# 6x5keyboard.net
KiCad netlist of a schematic drawn in EAGLE
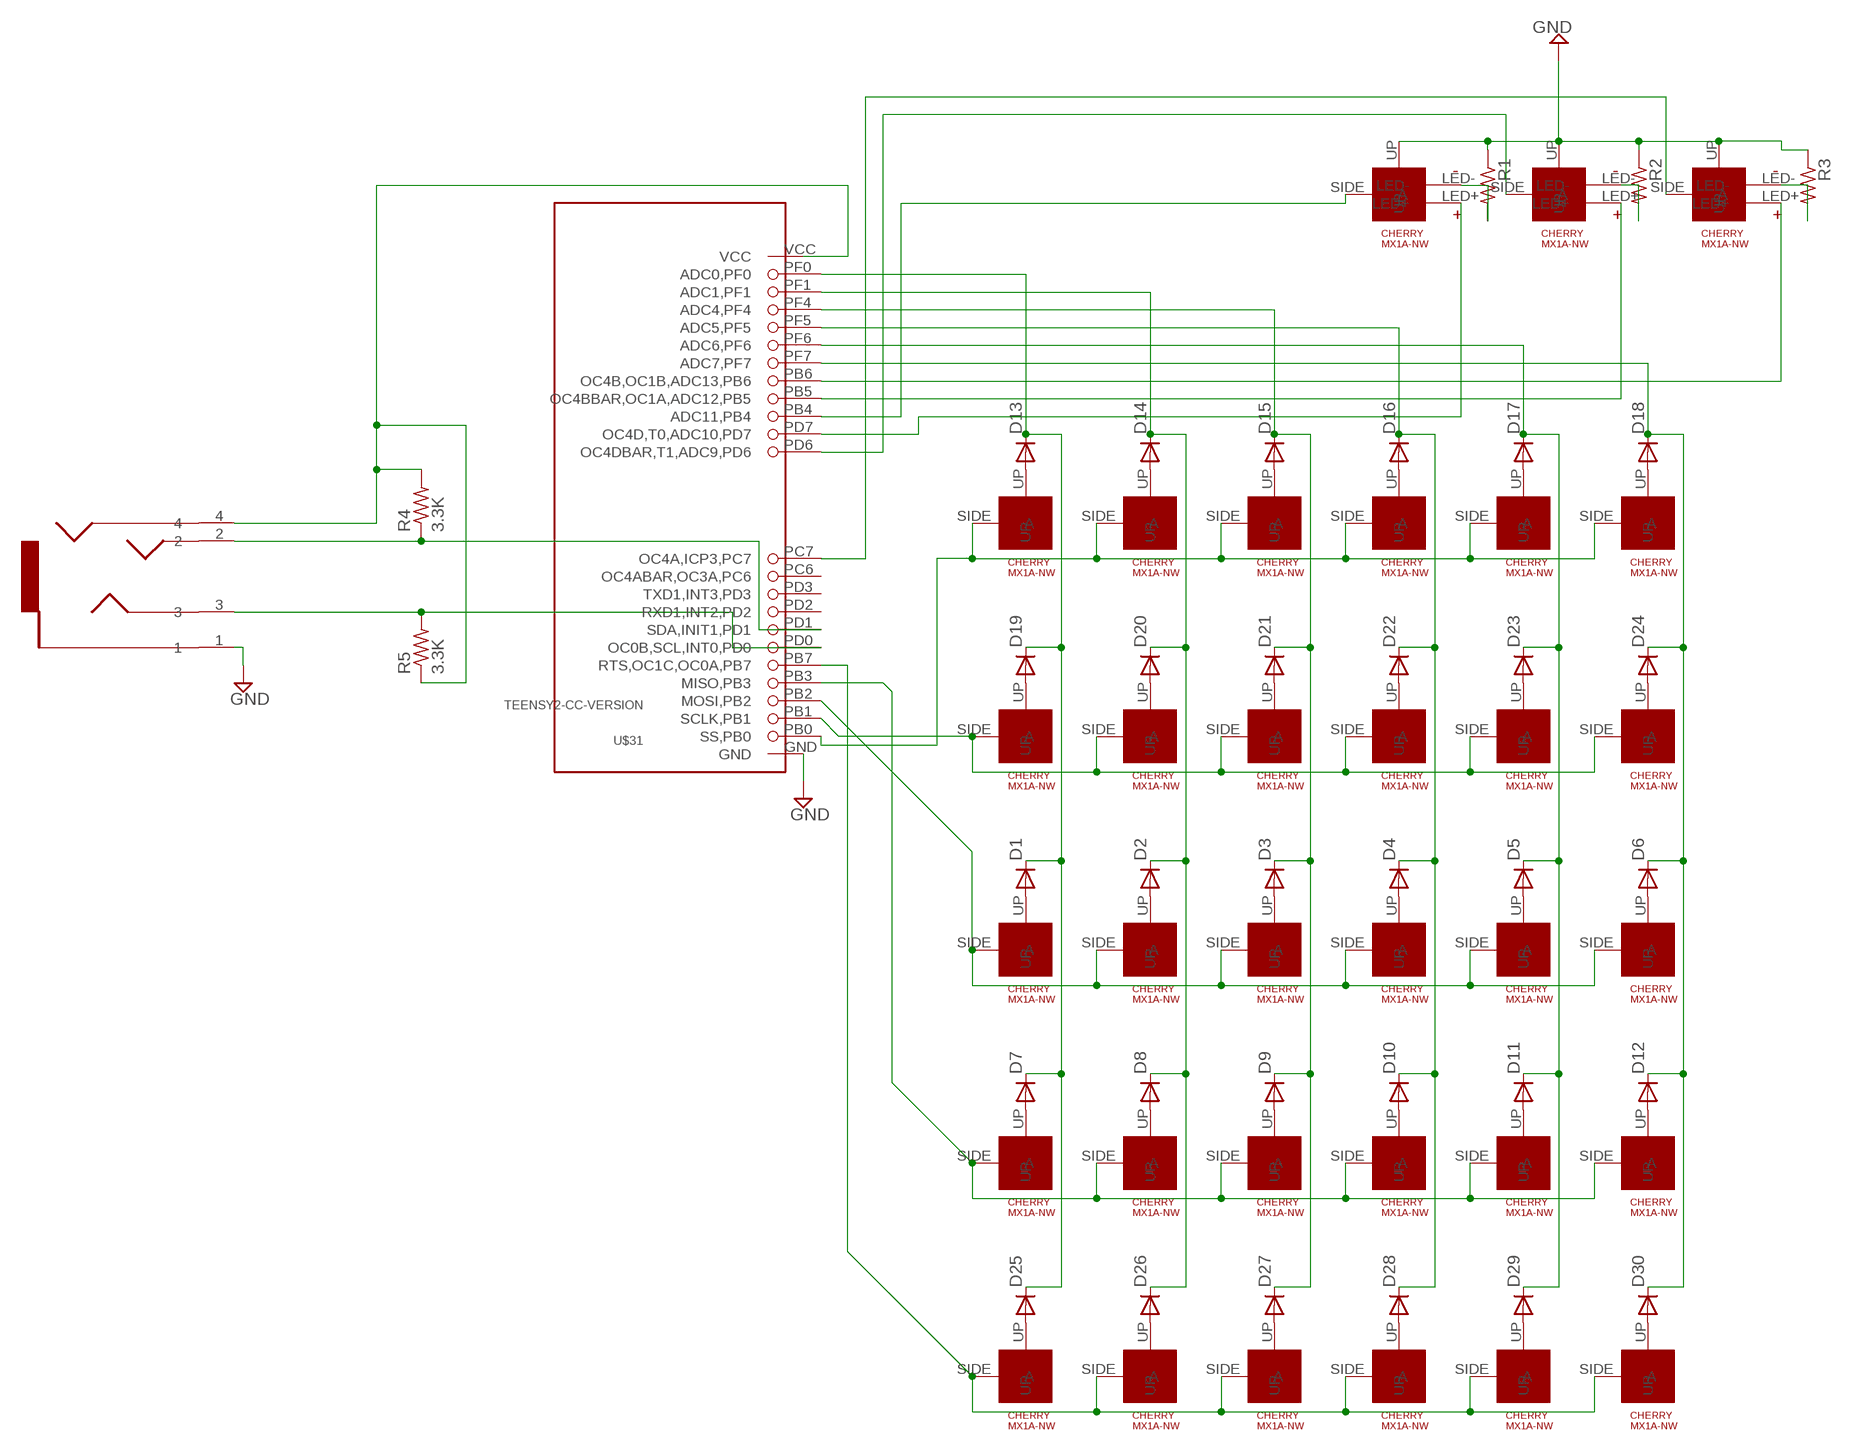
[diagram p0: schematic, sheet 1]

(export (version "E")
  (design (tool "Eeschema 10.0.6"))
  (components
    (comp (ref "COMM")
      (value "SJ-43514_HEADPHONES_3.5MM_X4")
      (footprint "eagle-import:SJ-43514_HEADPHONES-3.5MM_X4")
      (libsource (lib "eagle-import") (part "SJ-43514_HEADPHONES_3.5MM_X4"))
    )
    (comp (ref "D1")
      (value "1N4148DO35-7")
      (footprint "eagle-import:DO35-7")
      (libsource (lib "eagle-import") (part "1N4148DO35-7"))
    )
    (comp (ref "D2")
      (value "1N4148DO35-7")
      (footprint "eagle-import:DO35-7")
      (libsource (lib "eagle-import") (part "1N4148DO35-7"))
    )
    (comp (ref "D3")
      (value "1N4148DO35-7")
      (footprint "eagle-import:DO35-7")
      (libsource (lib "eagle-import") (part "1N4148DO35-7"))
    )
    (comp (ref "D4")
      (value "1N4148DO35-7")
      (footprint "eagle-import:DO35-7")
      (libsource (lib "eagle-import") (part "1N4148DO35-7"))
    )
    (comp (ref "D5")
      (value "1N4148DO35-7")
      (footprint "eagle-import:DO35-7")
      (libsource (lib "eagle-import") (part "1N4148DO35-7"))
    )
    (comp (ref "D6")
      (value "1N4148DO35-7")
      (footprint "eagle-import:DO35-7")
      (libsource (lib "eagle-import") (part "1N4148DO35-7"))
    )
    (comp (ref "D7")
      (value "1N4148DO35-7")
      (footprint "eagle-import:DO35-7")
      (libsource (lib "eagle-import") (part "1N4148DO35-7"))
    )
    (comp (ref "D8")
      (value "1N4148DO35-7")
      (footprint "eagle-import:DO35-7")
      (libsource (lib "eagle-import") (part "1N4148DO35-7"))
    )
    (comp (ref "D9")
      (value "1N4148DO35-7")
      (footprint "eagle-import:DO35-7")
      (libsource (lib "eagle-import") (part "1N4148DO35-7"))
    )
    (comp (ref "D10")
      (value "1N4148DO35-7")
      (footprint "eagle-import:DO35-7")
      (libsource (lib "eagle-import") (part "1N4148DO35-7"))
    )
    (comp (ref "D11")
      (value "1N4148DO35-7")
      (footprint "eagle-import:DO35-7")
      (libsource (lib "eagle-import") (part "1N4148DO35-7"))
    )
    (comp (ref "D12")
      (value "1N4148DO35-7")
      (footprint "eagle-import:DO35-7")
      (libsource (lib "eagle-import") (part "1N4148DO35-7"))
    )
    (comp (ref "D13")
      (value "1N4148DO35-7")
      (footprint "eagle-import:DO35-7")
      (libsource (lib "eagle-import") (part "1N4148DO35-7"))
    )
    (comp (ref "D14")
      (value "1N4148DO35-7")
      (footprint "eagle-import:DO35-7")
      (libsource (lib "eagle-import") (part "1N4148DO35-7"))
    )
    (comp (ref "D15")
      (value "1N4148DO35-7")
      (footprint "eagle-import:DO35-7")
      (libsource (lib "eagle-import") (part "1N4148DO35-7"))
    )
    (comp (ref "D16")
      (value "1N4148DO35-7")
      (footprint "eagle-import:DO35-7")
      (libsource (lib "eagle-import") (part "1N4148DO35-7"))
    )
    (comp (ref "D17")
      (value "1N4148DO35-7")
      (footprint "eagle-import:DO35-7")
      (libsource (lib "eagle-import") (part "1N4148DO35-7"))
    )
    (comp (ref "D18")
      (value "1N4148DO35-7")
      (footprint "eagle-import:DO35-7")
      (libsource (lib "eagle-import") (part "1N4148DO35-7"))
    )
    (comp (ref "D19")
      (value "1N4148DO35-7")
      (footprint "eagle-import:DO35-7")
      (libsource (lib "eagle-import") (part "1N4148DO35-7"))
    )
    (comp (ref "D20")
      (value "1N4148DO35-7")
      (footprint "eagle-import:DO35-7")
      (libsource (lib "eagle-import") (part "1N4148DO35-7"))
    )
    (comp (ref "D21")
      (value "1N4148DO35-7")
      (footprint "eagle-import:DO35-7")
      (libsource (lib "eagle-import") (part "1N4148DO35-7"))
    )
    (comp (ref "D22")
      (value "1N4148DO35-7")
      (footprint "eagle-import:DO35-7")
      (libsource (lib "eagle-import") (part "1N4148DO35-7"))
    )
    (comp (ref "D23")
      (value "1N4148DO35-7")
      (footprint "eagle-import:DO35-7")
      (libsource (lib "eagle-import") (part "1N4148DO35-7"))
    )
    (comp (ref "D24")
      (value "1N4148DO35-7")
      (footprint "eagle-import:DO35-7")
      (libsource (lib "eagle-import") (part "1N4148DO35-7"))
    )
    (comp (ref "D25")
      (value "1N4148DO35-7")
      (footprint "eagle-import:DO35-7")
      (libsource (lib "eagle-import") (part "1N4148DO35-7"))
    )
    (comp (ref "D26")
      (value "1N4148DO35-7")
      (footprint "eagle-import:DO35-7")
      (libsource (lib "eagle-import") (part "1N4148DO35-7"))
    )
    (comp (ref "D27")
      (value "1N4148DO35-7")
      (footprint "eagle-import:DO35-7")
      (libsource (lib "eagle-import") (part "1N4148DO35-7"))
    )
    (comp (ref "D28")
      (value "1N4148DO35-7")
      (footprint "eagle-import:DO35-7")
      (libsource (lib "eagle-import") (part "1N4148DO35-7"))
    )
    (comp (ref "D29")
      (value "1N4148DO35-7")
      (footprint "eagle-import:DO35-7")
      (libsource (lib "eagle-import") (part "1N4148DO35-7"))
    )
    (comp (ref "D30")
      (value "1N4148DO35-7")
      (footprint "eagle-import:DO35-7")
      (libsource (lib "eagle-import") (part "1N4148DO35-7"))
    )
    (comp (ref "R1")
      (value "R-US_0207/10")
      (footprint "eagle-import:0207_10")
      (libsource (lib "eagle-import") (part "R-US_0207/10"))
    )
    (comp (ref "R2")
      (value "R-US_0207/10")
      (footprint "eagle-import:0207_10")
      (libsource (lib "eagle-import") (part "R-US_0207/10"))
    )
    (comp (ref "R3")
      (value "R-US_0207/10")
      (footprint "eagle-import:0207_10")
      (libsource (lib "eagle-import") (part "R-US_0207/10"))
    )
    (comp (ref "R4")
      (value "3.3K")
      (footprint "eagle-import:0207_10")
      (libsource (lib "eagle-import") (part "resistor_R-US_0207/10"))
    )
    (comp (ref "R5")
      (value "3.3K")
      (footprint "eagle-import:0207_10")
      (libsource (lib "eagle-import") (part "resistor_R-US_0207/10"))
    )
    (comp (ref "U$1")
      (value "CHERRY-MX1A-E1NW")
      (footprint "eagle-import:CHERRYMX-NN")
      (libsource (lib "eagle-import") (part "CHERRY-MX1A-E1NW"))
    )
    (comp (ref "U$2")
      (value "CHERRY-MX1A-E1NW")
      (footprint "eagle-import:CHERRYMX-NN")
      (libsource (lib "eagle-import") (part "CHERRY-MX1A-E1NW"))
    )
    (comp (ref "U$3")
      (value "CHERRY-MX1A-E1NW")
      (footprint "eagle-import:CHERRYMX-NN")
      (libsource (lib "eagle-import") (part "CHERRY-MX1A-E1NW"))
    )
    (comp (ref "U$4")
      (value "CHERRY-MX1A-E1NW")
      (footprint "eagle-import:CHERRYMX-NN")
      (libsource (lib "eagle-import") (part "CHERRY-MX1A-E1NW"))
    )
    (comp (ref "U$5")
      (value "CHERRY-MX1A-E1NW")
      (footprint "eagle-import:CHERRYMX-NN")
      (libsource (lib "eagle-import") (part "CHERRY-MX1A-E1NW"))
    )
    (comp (ref "U$6")
      (value "CHERRY-MX1A-E1NW")
      (footprint "eagle-import:CHERRYMX-NN")
      (libsource (lib "eagle-import") (part "CHERRY-MX1A-E1NW"))
    )
    (comp (ref "U$7")
      (value "CHERRY-MX1A-E1NW")
      (footprint "eagle-import:CHERRYMX-NN")
      (libsource (lib "eagle-import") (part "CHERRY-MX1A-E1NW"))
    )
    (comp (ref "U$8")
      (value "CHERRY-MX1A-E1NW")
      (footprint "eagle-import:CHERRYMX-NN")
      (libsource (lib "eagle-import") (part "CHERRY-MX1A-E1NW"))
    )
    (comp (ref "U$9")
      (value "CHERRY-MX1A-E1NW")
      (footprint "eagle-import:CHERRYMX-NN")
      (libsource (lib "eagle-import") (part "CHERRY-MX1A-E1NW"))
    )
    (comp (ref "U$10")
      (value "CHERRY-MX1A-E1NW")
      (footprint "eagle-import:CHERRYMX-NN")
      (libsource (lib "eagle-import") (part "CHERRY-MX1A-E1NW"))
    )
    (comp (ref "U$11")
      (value "CHERRY-MX1A-E1NW")
      (footprint "eagle-import:CHERRYMX-NN")
      (libsource (lib "eagle-import") (part "CHERRY-MX1A-E1NW"))
    )
    (comp (ref "U$12")
      (value "CHERRY-MX1A-E1NW")
      (footprint "eagle-import:CHERRYMX-NN")
      (libsource (lib "eagle-import") (part "CHERRY-MX1A-E1NW"))
    )
    (comp (ref "U$13")
      (value "CHERRY-MX1A-E1NW")
      (footprint "eagle-import:CHERRYMX-NN")
      (libsource (lib "eagle-import") (part "CHERRY-MX1A-E1NW"))
    )
    (comp (ref "U$14")
      (value "CHERRY-MX1A-E1NW")
      (footprint "eagle-import:CHERRYMX-NN")
      (libsource (lib "eagle-import") (part "CHERRY-MX1A-E1NW"))
    )
    (comp (ref "U$15")
      (value "CHERRY-MX1A-E1NW")
      (footprint "eagle-import:CHERRYMX-NN")
      (libsource (lib "eagle-import") (part "CHERRY-MX1A-E1NW"))
    )
    (comp (ref "U$16")
      (value "CHERRY-MX1A-E1NW")
      (footprint "eagle-import:CHERRYMX-NN")
      (libsource (lib "eagle-import") (part "CHERRY-MX1A-E1NW"))
    )
    (comp (ref "U$17")
      (value "CHERRY-MX1A-E1NW")
      (footprint "eagle-import:CHERRYMX-NN")
      (libsource (lib "eagle-import") (part "CHERRY-MX1A-E1NW"))
    )
    (comp (ref "U$18")
      (value "CHERRY-MX1A-E1NW")
      (footprint "eagle-import:CHERRYMX-NN")
      (libsource (lib "eagle-import") (part "CHERRY-MX1A-E1NW"))
    )
    (comp (ref "U$19")
      (value "CHERRY-MX1A-E1NW")
      (footprint "eagle-import:CHERRYMX-NN")
      (libsource (lib "eagle-import") (part "CHERRY-MX1A-E1NW"))
    )
    (comp (ref "U$20")
      (value "CHERRY-MX1A-E1NW")
      (footprint "eagle-import:CHERRYMX-NN")
      (libsource (lib "eagle-import") (part "CHERRY-MX1A-E1NW"))
    )
    (comp (ref "U$21")
      (value "CHERRY-MX1A-E1NW")
      (footprint "eagle-import:CHERRYMX-NN")
      (libsource (lib "eagle-import") (part "CHERRY-MX1A-E1NW"))
    )
    (comp (ref "U$22")
      (value "CHERRY-MX1A-E1NW")
      (footprint "eagle-import:CHERRYMX-NN")
      (libsource (lib "eagle-import") (part "CHERRY-MX1A-E1NW"))
    )
    (comp (ref "U$23")
      (value "CHERRY-MX1A-E1NW")
      (footprint "eagle-import:CHERRYMX-NN")
      (libsource (lib "eagle-import") (part "CHERRY-MX1A-E1NW"))
    )
    (comp (ref "U$24")
      (value "CHERRY-MX1A-E1NW")
      (footprint "eagle-import:CHERRYMX-NN")
      (libsource (lib "eagle-import") (part "CHERRY-MX1A-E1NW"))
    )
    (comp (ref "U$25")
      (value "CHERRY-MX1A-E1NW")
      (footprint "eagle-import:CHERRYMX-NN")
      (libsource (lib "eagle-import") (part "CHERRY-MX1A-E1NW"))
    )
    (comp (ref "U$26")
      (value "CHERRY-MX1A-E1NW")
      (footprint "eagle-import:CHERRYMX-NN")
      (libsource (lib "eagle-import") (part "CHERRY-MX1A-E1NW"))
    )
    (comp (ref "U$27")
      (value "CHERRY-MX1A-E1NW")
      (footprint "eagle-import:CHERRYMX-NN")
      (libsource (lib "eagle-import") (part "CHERRY-MX1A-E1NW"))
    )
    (comp (ref "U$28")
      (value "CHERRY-MX1A-E1NW")
      (footprint "eagle-import:CHERRYMX-NN")
      (libsource (lib "eagle-import") (part "CHERRY-MX1A-E1NW"))
    )
    (comp (ref "U$29")
      (value "CHERRY-MX1A-E1NW")
      (footprint "eagle-import:CHERRYMX-NN")
      (libsource (lib "eagle-import") (part "CHERRY-MX1A-E1NW"))
    )
    (comp (ref "U$30")
      (value "CHERRY-MX1A-E1NW")
      (footprint "eagle-import:CHERRYMX-NN")
      (libsource (lib "eagle-import") (part "CHERRY-MX1A-E1NW"))
    )
    (comp (ref "U$31")
      (value "TEENSY2-CC-VERSION")
      (footprint "eagle-import:TEENSY2")
      (libsource (lib "eagle-import") (part "TEENSY2-CC-VERSION"))
    )
    (comp (ref "U$32")
      (value "CHERRY-MX1A-E1NW-LED")
      (footprint "eagle-import:CHERRYMX-NN-LED")
      (libsource (lib "eagle-import") (part "CHERRY-MX1A-E1NW-LED"))
    )
    (comp (ref "U$33")
      (value "CHERRY-MX1A-E1NW-LED")
      (footprint "eagle-import:CHERRYMX-NN-LED")
      (libsource (lib "eagle-import") (part "CHERRY-MX1A-E1NW-LED"))
    )
    (comp (ref "U$34")
      (value "CHERRY-MX1A-E1NW-LED")
      (footprint "eagle-import:CHERRYMX-NN-LED")
      (libsource (lib "eagle-import") (part "CHERRY-MX1A-E1NW-LED"))
    )
  )
  (nets
    (net (code "1") (name "GND") (class "Default")
      (node (ref "COMM") (pin "1") (pinfunction "1_1") (pintype "bidirectional"))
      (node (ref "R1") (pin "1") (pinfunction "1_1") (pintype "passive"))
      (node (ref "R2") (pin "1") (pinfunction "1_1") (pintype "passive"))
      (node (ref "R3") (pin "1") (pinfunction "1_1") (pintype "passive"))
      (node (ref "U$31") (pin "GND") (pinfunction "GND_GND") (pintype "power_in"))
      (node (ref "U$32") (pin "UP") (pinfunction "UP_UP") (pintype "bidirectional"))
      (node (ref "U$33") (pin "UP") (pinfunction "UP_UP") (pintype "bidirectional"))
      (node (ref "U$34") (pin "UP") (pinfunction "UP_UP") (pintype "bidirectional"))
    )
    (net (code "2") (name "Net-(COMM-Pad4)") (class "Default")
      (node (ref "COMM") (pin "4") (pinfunction "4_4") (pintype "bidirectional"))
      (node (ref "R4") (pin "2") (pinfunction "2_2") (pintype "passive"))
      (node (ref "R5") (pin "1") (pinfunction "1_1") (pintype "passive"))
      (node (ref "U$31") (pin "VCC") (pinfunction "VCC_VCC") (pintype "power_in"))
    )
    (net (code "3") (name "Net-(D1-PadA)") (class "Default")
      (node (ref "D1") (pin "A") (pinfunction "A_A") (pintype "passive"))
      (node (ref "U$2") (pin "UP") (pinfunction "UP_UP") (pintype "bidirectional"))
    )
    (net (code "4") (name "Net-(D2-PadA)") (class "Default")
      (node (ref "D2") (pin "A") (pinfunction "A_A") (pintype "passive"))
      (node (ref "U$1") (pin "UP") (pinfunction "UP_UP") (pintype "bidirectional"))
    )
    (net (code "5") (name "Net-(D3-PadA)") (class "Default")
      (node (ref "D3") (pin "A") (pinfunction "A_A") (pintype "passive"))
      (node (ref "U$3") (pin "UP") (pinfunction "UP_UP") (pintype "bidirectional"))
    )
    (net (code "6") (name "Net-(D4-PadA)") (class "Default")
      (node (ref "D4") (pin "A") (pinfunction "A_A") (pintype "passive"))
      (node (ref "U$4") (pin "UP") (pinfunction "UP_UP") (pintype "bidirectional"))
    )
    (net (code "7") (name "Net-(D5-PadA)") (class "Default")
      (node (ref "D5") (pin "A") (pinfunction "A_A") (pintype "passive"))
      (node (ref "U$5") (pin "UP") (pinfunction "UP_UP") (pintype "bidirectional"))
    )
    (net (code "8") (name "Net-(D6-PadA)") (class "Default")
      (node (ref "D6") (pin "A") (pinfunction "A_A") (pintype "passive"))
      (node (ref "U$6") (pin "UP") (pinfunction "UP_UP") (pintype "bidirectional"))
    )
    (net (code "9") (name "Net-(D7-PadA)") (class "Default")
      (node (ref "D7") (pin "A") (pinfunction "A_A") (pintype "passive"))
      (node (ref "U$7") (pin "UP") (pinfunction "UP_UP") (pintype "bidirectional"))
    )
    (net (code "10") (name "Net-(D8-PadA)") (class "Default")
      (node (ref "D8") (pin "A") (pinfunction "A_A") (pintype "passive"))
      (node (ref "U$8") (pin "UP") (pinfunction "UP_UP") (pintype "bidirectional"))
    )
    (net (code "11") (name "Net-(D9-PadA)") (class "Default")
      (node (ref "D9") (pin "A") (pinfunction "A_A") (pintype "passive"))
      (node (ref "U$9") (pin "UP") (pinfunction "UP_UP") (pintype "bidirectional"))
    )
    (net (code "12") (name "Net-(D10-PadA)") (class "Default")
      (node (ref "D10") (pin "A") (pinfunction "A_A") (pintype "passive"))
      (node (ref "U$10") (pin "UP") (pinfunction "UP_UP") (pintype "bidirectional"))
    )
    (net (code "13") (name "Net-(D11-PadA)") (class "Default")
      (node (ref "D11") (pin "A") (pinfunction "A_A") (pintype "passive"))
      (node (ref "U$11") (pin "UP") (pinfunction "UP_UP") (pintype "bidirectional"))
    )
    (net (code "14") (name "Net-(D12-PadA)") (class "Default")
      (node (ref "D12") (pin "A") (pinfunction "A_A") (pintype "passive"))
      (node (ref "U$12") (pin "UP") (pinfunction "UP_UP") (pintype "bidirectional"))
    )
    (net (code "15") (name "Net-(D13-PadA)") (class "Default")
      (node (ref "D13") (pin "A") (pinfunction "A_A") (pintype "passive"))
      (node (ref "U$13") (pin "UP") (pinfunction "UP_UP") (pintype "bidirectional"))
    )
    (net (code "16") (name "Net-(D14-PadA)") (class "Default")
      (node (ref "D14") (pin "A") (pinfunction "A_A") (pintype "passive"))
      (node (ref "U$14") (pin "UP") (pinfunction "UP_UP") (pintype "bidirectional"))
    )
    (net (code "17") (name "Net-(D15-PadA)") (class "Default")
      (node (ref "D15") (pin "A") (pinfunction "A_A") (pintype "passive"))
      (node (ref "U$15") (pin "UP") (pinfunction "UP_UP") (pintype "bidirectional"))
    )
    (net (code "18") (name "Net-(D16-PadA)") (class "Default")
      (node (ref "D16") (pin "A") (pinfunction "A_A") (pintype "passive"))
      (node (ref "U$16") (pin "UP") (pinfunction "UP_UP") (pintype "bidirectional"))
    )
    (net (code "19") (name "Net-(D17-PadA)") (class "Default")
      (node (ref "D17") (pin "A") (pinfunction "A_A") (pintype "passive"))
      (node (ref "U$17") (pin "UP") (pinfunction "UP_UP") (pintype "bidirectional"))
    )
    (net (code "20") (name "Net-(D18-PadA)") (class "Default")
      (node (ref "D18") (pin "A") (pinfunction "A_A") (pintype "passive"))
      (node (ref "U$18") (pin "UP") (pinfunction "UP_UP") (pintype "bidirectional"))
    )
    (net (code "21") (name "Net-(D19-PadA)") (class "Default")
      (node (ref "D19") (pin "A") (pinfunction "A_A") (pintype "passive"))
      (node (ref "U$19") (pin "UP") (pinfunction "UP_UP") (pintype "bidirectional"))
    )
    (net (code "22") (name "Net-(D20-PadA)") (class "Default")
      (node (ref "D20") (pin "A") (pinfunction "A_A") (pintype "passive"))
      (node (ref "U$20") (pin "UP") (pinfunction "UP_UP") (pintype "bidirectional"))
    )
    (net (code "23") (name "Net-(D21-PadA)") (class "Default")
      (node (ref "D21") (pin "A") (pinfunction "A_A") (pintype "passive"))
      (node (ref "U$21") (pin "UP") (pinfunction "UP_UP") (pintype "bidirectional"))
    )
    (net (code "24") (name "Net-(D22-PadA)") (class "Default")
      (node (ref "D22") (pin "A") (pinfunction "A_A") (pintype "passive"))
      (node (ref "U$22") (pin "UP") (pinfunction "UP_UP") (pintype "bidirectional"))
    )
    (net (code "25") (name "Net-(D23-PadA)") (class "Default")
      (node (ref "D23") (pin "A") (pinfunction "A_A") (pintype "passive"))
      (node (ref "U$23") (pin "UP") (pinfunction "UP_UP") (pintype "bidirectional"))
    )
    (net (code "26") (name "Net-(D24-PadA)") (class "Default")
      (node (ref "D24") (pin "A") (pinfunction "A_A") (pintype "passive"))
      (node (ref "U$24") (pin "UP") (pinfunction "UP_UP") (pintype "bidirectional"))
    )
    (net (code "27") (name "Net-(D25-PadA)") (class "Default")
      (node (ref "D25") (pin "A") (pinfunction "A_A") (pintype "passive"))
      (node (ref "U$25") (pin "UP") (pinfunction "UP_UP") (pintype "bidirectional"))
    )
    (net (code "28") (name "Net-(D26-PadA)") (class "Default")
      (node (ref "D26") (pin "A") (pinfunction "A_A") (pintype "passive"))
      (node (ref "U$26") (pin "UP") (pinfunction "UP_UP") (pintype "bidirectional"))
    )
    (net (code "29") (name "Net-(D27-PadA)") (class "Default")
      (node (ref "D27") (pin "A") (pinfunction "A_A") (pintype "passive"))
      (node (ref "U$27") (pin "UP") (pinfunction "UP_UP") (pintype "bidirectional"))
    )
    (net (code "30") (name "Net-(D28-PadA)") (class "Default")
      (node (ref "D28") (pin "A") (pinfunction "A_A") (pintype "passive"))
      (node (ref "U$28") (pin "UP") (pinfunction "UP_UP") (pintype "bidirectional"))
    )
    (net (code "31") (name "Net-(D29-PadA)") (class "Default")
      (node (ref "D29") (pin "A") (pinfunction "A_A") (pintype "passive"))
      (node (ref "U$29") (pin "UP") (pinfunction "UP_UP") (pintype "bidirectional"))
    )
    (net (code "32") (name "Net-(D30-PadA)") (class "Default")
      (node (ref "D30") (pin "A") (pinfunction "A_A") (pintype "passive"))
      (node (ref "U$30") (pin "UP") (pinfunction "UP_UP") (pintype "bidirectional"))
    )
    (net (code "33") (name "Net-(R1-Pad2)") (class "Default")
      (node (ref "R1") (pin "2") (pinfunction "2_2") (pintype "passive"))
      (node (ref "U$32") (pin "LED-") (pinfunction "LED-_LED-") (pintype "bidirectional"))
    )
    (net (code "34") (name "Net-(R2-Pad2)") (class "Default")
      (node (ref "R2") (pin "2") (pinfunction "2_2") (pintype "passive"))
      (node (ref "U$33") (pin "LED-") (pinfunction "LED-_LED-") (pintype "bidirectional"))
    )
    (net (code "35") (name "Net-(R3-Pad2)") (class "Default")
      (node (ref "R3") (pin "2") (pinfunction "2_2") (pintype "passive"))
      (node (ref "U$34") (pin "LED-") (pinfunction "LED-_LED-") (pintype "bidirectional"))
    )
    (net (code "36") (name "Net-(U$1-A)") (class "Default")
      (node (ref "U$1") (pin "SIDE") (pinfunction "A_SIDE") (pintype "bidirectional"))
      (node (ref "U$2") (pin "SIDE") (pinfunction "A_SIDE") (pintype "bidirectional"))
      (node (ref "U$3") (pin "SIDE") (pinfunction "A_SIDE") (pintype "bidirectional"))
      (node (ref "U$31") (pin "PB2") (pinfunction "MOSI,PB2_PB2") (pintype "bidirectional"))
      (node (ref "U$4") (pin "SIDE") (pinfunction "A_SIDE") (pintype "bidirectional"))
      (node (ref "U$5") (pin "SIDE") (pinfunction "A_SIDE") (pintype "bidirectional"))
      (node (ref "U$6") (pin "SIDE") (pinfunction "A_SIDE") (pintype "bidirectional"))
    )
    (net (code "37") (name "Net-(U$10-A)") (class "Default")
      (node (ref "U$10") (pin "SIDE") (pinfunction "A_SIDE") (pintype "bidirectional"))
      (node (ref "U$11") (pin "SIDE") (pinfunction "A_SIDE") (pintype "bidirectional"))
      (node (ref "U$12") (pin "SIDE") (pinfunction "A_SIDE") (pintype "bidirectional"))
      (node (ref "U$31") (pin "PB3") (pinfunction "MISO,PB3_PB3") (pintype "bidirectional"))
      (node (ref "U$7") (pin "SIDE") (pinfunction "A_SIDE") (pintype "bidirectional"))
      (node (ref "U$8") (pin "SIDE") (pinfunction "A_SIDE") (pintype "bidirectional"))
      (node (ref "U$9") (pin "SIDE") (pinfunction "A_SIDE") (pintype "bidirectional"))
    )
    (net (code "38") (name "Net-(U$13-A)") (class "Default")
      (node (ref "U$13") (pin "SIDE") (pinfunction "A_SIDE") (pintype "bidirectional"))
      (node (ref "U$14") (pin "SIDE") (pinfunction "A_SIDE") (pintype "bidirectional"))
      (node (ref "U$15") (pin "SIDE") (pinfunction "A_SIDE") (pintype "bidirectional"))
      (node (ref "U$16") (pin "SIDE") (pinfunction "A_SIDE") (pintype "bidirectional"))
      (node (ref "U$17") (pin "SIDE") (pinfunction "A_SIDE") (pintype "bidirectional"))
      (node (ref "U$18") (pin "SIDE") (pinfunction "A_SIDE") (pintype "bidirectional"))
      (node (ref "U$31") (pin "PB0") (pinfunction "SS,PB0_PB0") (pintype "bidirectional"))
    )
    (net (code "39") (name "Net-(U$19-A)") (class "Default")
      (node (ref "U$19") (pin "SIDE") (pinfunction "A_SIDE") (pintype "bidirectional"))
      (node (ref "U$20") (pin "SIDE") (pinfunction "A_SIDE") (pintype "bidirectional"))
      (node (ref "U$21") (pin "SIDE") (pinfunction "A_SIDE") (pintype "bidirectional"))
      (node (ref "U$22") (pin "SIDE") (pinfunction "A_SIDE") (pintype "bidirectional"))
      (node (ref "U$23") (pin "SIDE") (pinfunction "A_SIDE") (pintype "bidirectional"))
      (node (ref "U$24") (pin "SIDE") (pinfunction "A_SIDE") (pintype "bidirectional"))
      (node (ref "U$31") (pin "PB1") (pinfunction "SCLK,PB1_PB1") (pintype "bidirectional"))
    )
    (net (code "40") (name "Net-(U$25-A)") (class "Default")
      (node (ref "U$25") (pin "SIDE") (pinfunction "A_SIDE") (pintype "bidirectional"))
      (node (ref "U$26") (pin "SIDE") (pinfunction "A_SIDE") (pintype "bidirectional"))
      (node (ref "U$27") (pin "SIDE") (pinfunction "A_SIDE") (pintype "bidirectional"))
      (node (ref "U$28") (pin "SIDE") (pinfunction "A_SIDE") (pintype "bidirectional"))
      (node (ref "U$29") (pin "SIDE") (pinfunction "A_SIDE") (pintype "bidirectional"))
      (node (ref "U$30") (pin "SIDE") (pinfunction "A_SIDE") (pintype "bidirectional"))
      (node (ref "U$31") (pin "PB7") (pinfunction "RTS,OC1C,OC0A,PB7_PB7") (pintype "bidirectional"))
    )
    (net (code "41") (name "Net-(U$31-ADC0,PF0)") (class "Default")
      (node (ref "D1") (pin "C") (pinfunction "C_C") (pintype "passive"))
      (node (ref "D13") (pin "C") (pinfunction "C_C") (pintype "passive"))
      (node (ref "D19") (pin "C") (pinfunction "C_C") (pintype "passive"))
      (node (ref "D25") (pin "C") (pinfunction "C_C") (pintype "passive"))
      (node (ref "D7") (pin "C") (pinfunction "C_C") (pintype "passive"))
      (node (ref "U$31") (pin "PF0") (pinfunction "ADC0,PF0_PF0") (pintype "bidirectional"))
    )
    (net (code "42") (name "Net-(U$31-ADC1,PF1)") (class "Default")
      (node (ref "D14") (pin "C") (pinfunction "C_C") (pintype "passive"))
      (node (ref "D2") (pin "C") (pinfunction "C_C") (pintype "passive"))
      (node (ref "D20") (pin "C") (pinfunction "C_C") (pintype "passive"))
      (node (ref "D26") (pin "C") (pinfunction "C_C") (pintype "passive"))
      (node (ref "D8") (pin "C") (pinfunction "C_C") (pintype "passive"))
      (node (ref "U$31") (pin "PF1") (pinfunction "ADC1,PF1_PF1") (pintype "bidirectional"))
    )
    (net (code "43") (name "Net-(U$31-ADC4,PF4)") (class "Default")
      (node (ref "D15") (pin "C") (pinfunction "C_C") (pintype "passive"))
      (node (ref "D21") (pin "C") (pinfunction "C_C") (pintype "passive"))
      (node (ref "D27") (pin "C") (pinfunction "C_C") (pintype "passive"))
      (node (ref "D3") (pin "C") (pinfunction "C_C") (pintype "passive"))
      (node (ref "D9") (pin "C") (pinfunction "C_C") (pintype "passive"))
      (node (ref "U$31") (pin "PF4") (pinfunction "ADC4,PF4_PF4") (pintype "bidirectional"))
    )
    (net (code "44") (name "Net-(U$31-ADC5,PF5)") (class "Default")
      (node (ref "D10") (pin "C") (pinfunction "C_C") (pintype "passive"))
      (node (ref "D16") (pin "C") (pinfunction "C_C") (pintype "passive"))
      (node (ref "D22") (pin "C") (pinfunction "C_C") (pintype "passive"))
      (node (ref "D28") (pin "C") (pinfunction "C_C") (pintype "passive"))
      (node (ref "D4") (pin "C") (pinfunction "C_C") (pintype "passive"))
      (node (ref "U$31") (pin "PF5") (pinfunction "ADC5,PF5_PF5") (pintype "bidirectional"))
    )
    (net (code "45") (name "Net-(U$31-ADC6,PF6)") (class "Default")
      (node (ref "D11") (pin "C") (pinfunction "C_C") (pintype "passive"))
      (node (ref "D17") (pin "C") (pinfunction "C_C") (pintype "passive"))
      (node (ref "D23") (pin "C") (pinfunction "C_C") (pintype "passive"))
      (node (ref "D29") (pin "C") (pinfunction "C_C") (pintype "passive"))
      (node (ref "D5") (pin "C") (pinfunction "C_C") (pintype "passive"))
      (node (ref "U$31") (pin "PF6") (pinfunction "ADC6,PF6_PF6") (pintype "bidirectional"))
    )
    (net (code "46") (name "Net-(U$31-ADC7,PF7)") (class "Default")
      (node (ref "D12") (pin "C") (pinfunction "C_C") (pintype "passive"))
      (node (ref "D18") (pin "C") (pinfunction "C_C") (pintype "passive"))
      (node (ref "D24") (pin "C") (pinfunction "C_C") (pintype "passive"))
      (node (ref "D30") (pin "C") (pinfunction "C_C") (pintype "passive"))
      (node (ref "D6") (pin "C") (pinfunction "C_C") (pintype "passive"))
      (node (ref "U$31") (pin "PF7") (pinfunction "ADC7,PF7_PF7") (pintype "bidirectional"))
    )
    (net (code "47") (name "Net-(U$31-ADC11,PB4)") (class "Default")
      (node (ref "U$31") (pin "PB4") (pinfunction "ADC11,PB4_PB4") (pintype "bidirectional"))
      (node (ref "U$32") (pin "SIDE") (pinfunction "A_SIDE") (pintype "bidirectional"))
    )
    (net (code "48") (name "Net-(U$31-OC0B,SCL,INT0,PD0)") (class "Default")
      (node (ref "COMM") (pin "3") (pinfunction "3_3") (pintype "bidirectional"))
      (node (ref "R5") (pin "2") (pinfunction "2_2") (pintype "passive"))
      (node (ref "U$31") (pin "PD0") (pinfunction "OC0B,SCL,INT0,PD0_PD0") (pintype "bidirectional"))
    )
    (net (code "49") (name "Net-(U$31-OC4A,ICP3,PC7)") (class "Default")
      (node (ref "U$31") (pin "PC7") (pinfunction "OC4A,ICP3,PC7_PC7") (pintype "bidirectional"))
      (node (ref "U$34") (pin "SIDE") (pinfunction "A_SIDE") (pintype "bidirectional"))
    )
    (net (code "50") (name "Net-(U$31-OC4B,OC1B,ADC13,PB6)") (class "Default")
      (node (ref "U$31") (pin "PB6") (pinfunction "OC4B,OC1B,ADC13,PB6_PB6") (pintype "bidirectional"))
      (node (ref "U$34") (pin "LED+") (pinfunction "LED+_LED+") (pintype "bidirectional"))
    )
    (net (code "51") (name "Net-(U$31-OC4BBAR,OC1A,ADC12,PB5)") (class "Default")
      (node (ref "U$31") (pin "PB5") (pinfunction "OC4BBAR,OC1A,ADC12,PB5_PB5") (pintype "bidirectional"))
      (node (ref "U$33") (pin "LED+") (pinfunction "LED+_LED+") (pintype "bidirectional"))
    )
    (net (code "52") (name "Net-(U$31-OC4D,T0,ADC10,PD7)") (class "Default")
      (node (ref "U$31") (pin "PD7") (pinfunction "OC4D,T0,ADC10,PD7_PD7") (pintype "bidirectional"))
      (node (ref "U$32") (pin "LED+") (pinfunction "LED+_LED+") (pintype "bidirectional"))
    )
    (net (code "53") (name "Net-(U$31-OC4DBAR,T1,ADC9,PD6)") (class "Default")
      (node (ref "U$31") (pin "PD6") (pinfunction "OC4DBAR,T1,ADC9,PD6_PD6") (pintype "bidirectional"))
      (node (ref "U$33") (pin "SIDE") (pinfunction "A_SIDE") (pintype "bidirectional"))
    )
    (net (code "54") (name "Net-(U$31-SDA,INIT1,PD1)") (class "Default")
      (node (ref "COMM") (pin "2") (pinfunction "2_2") (pintype "bidirectional"))
      (node (ref "R4") (pin "1") (pinfunction "1_1") (pintype "passive"))
      (node (ref "U$31") (pin "PD1") (pinfunction "SDA,INIT1,PD1_PD1") (pintype "bidirectional"))
    )
    (net (code "55") (name "unconnected-(U$31-OC4ABAR,OC3A,PC6-PadPC6)") (class "Default")
      (node (ref "U$31") (pin "PC6") (pinfunction "OC4ABAR,OC3A,PC6_PC6") (pintype "bidirectional"))
    )
    (net (code "56") (name "unconnected-(U$31-RXD1,INT2,PD2-PadPD2)") (class "Default")
      (node (ref "U$31") (pin "PD2") (pinfunction "RXD1,INT2,PD2_PD2") (pintype "bidirectional"))
    )
    (net (code "57") (name "unconnected-(U$31-TXD1,INT3,PD3-PadPD3)") (class "Default")
      (node (ref "U$31") (pin "PD3") (pinfunction "TXD1,INT3,PD3_PD3") (pintype "bidirectional"))
    )
  )
)
